# ICEBoard.net
KiCad netlist of a schematic drawn in Altium Designer
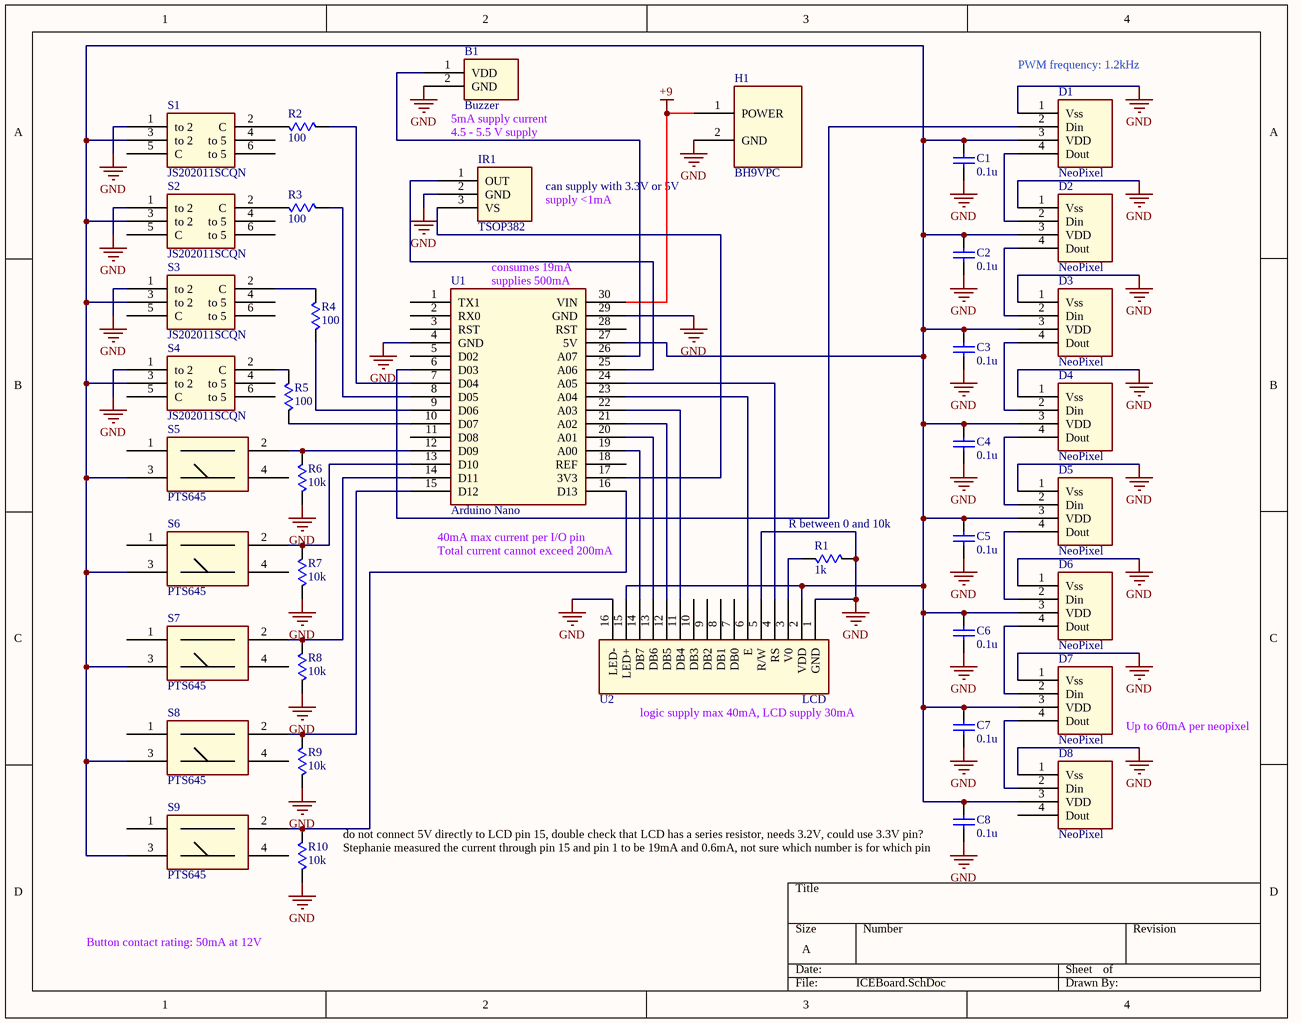
[diagram p0: ICEBoard.SchDoc]

(export (version "E")
  (design (tool "Eeschema 10.0.6"))
  (components
    (comp (ref "B1") (value "Buzzer") (footprint "TP124005") (libsource (lib "TP124005") (part "TP124005")))
    (comp (ref "C1") (value "0.1u") (footprint "Capacitor") (libsource (lib "Capacitor") (part "Capacitor")))
    (comp (ref "C2") (value "0.1u") (footprint "Capacitor") (libsource (lib "Capacitor") (part "Capacitor")))
    (comp (ref "C3") (value "0.1u") (footprint "Capacitor") (libsource (lib "Capacitor") (part "Capacitor")))
    (comp (ref "C4") (value "0.1u") (footprint "Capacitor") (libsource (lib "Capacitor") (part "Capacitor")))
    (comp (ref "C5") (value "0.1u") (footprint "Capacitor") (libsource (lib "Capacitor") (part "Capacitor")))
    (comp (ref "C6") (value "0.1u") (footprint "Capacitor") (libsource (lib "Capacitor") (part "Capacitor")))
    (comp (ref "C7") (value "0.1u") (footprint "Capacitor") (libsource (lib "Capacitor") (part "Capacitor")))
    (comp (ref "C8") (value "0.1u") (footprint "Capacitor") (libsource (lib "Capacitor") (part "Capacitor")))
    (comp (ref "D1") (value "NeoPixel") (footprint "NeoPixel") (libsource (lib "NeoPixel") (part "NeoPixel")))
    (comp (ref "D2") (value "NeoPixel") (footprint "NeoPixel") (libsource (lib "NeoPixel") (part "NeoPixel")))
    (comp (ref "D3") (value "NeoPixel") (footprint "NeoPixel") (libsource (lib "NeoPixel") (part "NeoPixel")))
    (comp (ref "D4") (value "NeoPixel") (footprint "NeoPixel") (libsource (lib "NeoPixel") (part "NeoPixel")))
    (comp (ref "D5") (value "NeoPixel") (footprint "NeoPixel") (libsource (lib "NeoPixel") (part "NeoPixel")))
    (comp (ref "D6") (value "NeoPixel") (footprint "NeoPixel") (libsource (lib "NeoPixel") (part "NeoPixel")))
    (comp (ref "D7") (value "NeoPixel") (footprint "NeoPixel") (libsource (lib "NeoPixel") (part "NeoPixel")))
    (comp (ref "D8") (value "NeoPixel") (footprint "NeoPixel") (libsource (lib "NeoPixel") (part "NeoPixel")))
    (comp (ref "H1") (value "BH9VPC") (footprint "BH9VPC") (libsource (lib "BH9VPC") (part "BH9VPC")))
    (comp (ref "IR1") (value "TSOP382") (footprint "TSOP382") (libsource (lib "TSOP382") (part "TSOP382")))
    (comp (ref "R1") (value "1k") (footprint "Resistor1608") (libsource (lib "Resistor") (part "Resistor")))
    (comp (ref "R2") (value "100") (footprint "Resistor1608") (libsource (lib "Resistor") (part "Resistor")))
    (comp (ref "R3") (value "100") (footprint "Resistor1608") (libsource (lib "Resistor") (part "Resistor")))
    (comp (ref "R4") (value "100") (footprint "Resistor1608") (libsource (lib "Resistor") (part "Resistor")))
    (comp (ref "R5") (value "100") (footprint "Resistor1608") (libsource (lib "Resistor") (part "Resistor")))
    (comp (ref "R6") (value "10k") (footprint "Resistor1608") (libsource (lib "Resistor") (part "Resistor")))
    (comp (ref "R7") (value "10k") (footprint "Resistor1608") (libsource (lib "Resistor") (part "Resistor")))
    (comp (ref "R8") (value "10k") (footprint "Resistor1608") (libsource (lib "Resistor") (part "Resistor")))
    (comp (ref "R9") (value "10k") (footprint "Resistor1608") (libsource (lib "Resistor") (part "Resistor")))
    (comp (ref "R10") (value "10k") (footprint "Resistor1608") (libsource (lib "Resistor") (part "Resistor")))
    (comp (ref "S1")
      (value "JS202011SCQN")
      (footprint "JS202011SCQN")
      (libsource (lib "JS202011SCQN") (part "JS202011SCQN"))
    )
    (comp (ref "S2")
      (value "JS202011SCQN")
      (footprint "JS202011SCQN")
      (libsource (lib "JS202011SCQN") (part "JS202011SCQN"))
    )
    (comp (ref "S3")
      (value "JS202011SCQN")
      (footprint "JS202011SCQN")
      (libsource (lib "JS202011SCQN") (part "JS202011SCQN"))
    )
    (comp (ref "S4")
      (value "JS202011SCQN")
      (footprint "JS202011SCQN")
      (libsource (lib "JS202011SCQN") (part "JS202011SCQN"))
    )
    (comp (ref "S5") (value "PTS645") (footprint "PTS645") (libsource (lib "PTS645") (part "PTS645")))
    (comp (ref "S6") (value "PTS645") (footprint "PTS645") (libsource (lib "PTS645") (part "PTS645")))
    (comp (ref "S7") (value "PTS645") (footprint "PTS645") (libsource (lib "PTS645") (part "PTS645")))
    (comp (ref "S8") (value "PTS645") (footprint "PTS645") (libsource (lib "PTS645") (part "PTS645")))
    (comp (ref "S9") (value "PTS645") (footprint "PTS645") (libsource (lib "PTS645") (part "PTS645")))
    (comp (ref "U1")
      (value "Arduino Nano")
      (footprint "ArduinoNano")
      (libsource (lib "ArduinoNano") (part "ArduinoNano"))
    )
    (comp (ref "U2")
      (value "LCD")
      (footprint "TC1602A-01T")
      (libsource (lib "TC1602A-01T") (part "TC1602A-01T"))
    )
  )
  (nets
    (net (code "1") (name "+9") (class "Default")
      (node (ref "H1") (pin "1") (pinfunction "POWER_1") (pintype "passive"))
      (node (ref "U1") (pin "30") (pinfunction "VIN_30") (pintype "passive"))
    )
    (net (code "2") (name "GND") (class "Default")
      (node (ref "B1") (pin "2") (pinfunction "GND_2") (pintype "passive"))
      (node (ref "C1") (pin "2") (pinfunction "2_2") (pintype "passive"))
      (node (ref "C2") (pin "2") (pinfunction "2_2") (pintype "passive"))
      (node (ref "C3") (pin "2") (pinfunction "2_2") (pintype "passive"))
      (node (ref "C4") (pin "2") (pinfunction "2_2") (pintype "passive"))
      (node (ref "C5") (pin "2") (pinfunction "2_2") (pintype "passive"))
      (node (ref "C6") (pin "2") (pinfunction "2_2") (pintype "passive"))
      (node (ref "C7") (pin "2") (pinfunction "2_2") (pintype "passive"))
      (node (ref "C8") (pin "2") (pinfunction "2_2") (pintype "passive"))
      (node (ref "D1") (pin "1") (pinfunction "Vss_1") (pintype "passive"))
      (node (ref "D2") (pin "1") (pinfunction "Vss_1") (pintype "passive"))
      (node (ref "D3") (pin "1") (pinfunction "Vss_1") (pintype "passive"))
      (node (ref "D4") (pin "1") (pinfunction "Vss_1") (pintype "passive"))
      (node (ref "D5") (pin "1") (pinfunction "Vss_1") (pintype "passive"))
      (node (ref "D6") (pin "1") (pinfunction "Vss_1") (pintype "passive"))
      (node (ref "D7") (pin "1") (pinfunction "Vss_1") (pintype "passive"))
      (node (ref "D8") (pin "1") (pinfunction "Vss_1") (pintype "passive"))
      (node (ref "H1") (pin "2") (pinfunction "GND_2") (pintype "passive"))
      (node (ref "IR1") (pin "2") (pinfunction "GND_2") (pintype "passive"))
      (node (ref "R1") (pin "1") (pinfunction "1_1") (pintype "passive"))
      (node (ref "R10") (pin "1") (pinfunction "1_1") (pintype "passive"))
      (node (ref "R6") (pin "1") (pinfunction "1_1") (pintype "passive"))
      (node (ref "R7") (pin "1") (pinfunction "1_1") (pintype "passive"))
      (node (ref "R8") (pin "1") (pinfunction "1_1") (pintype "passive"))
      (node (ref "R9") (pin "1") (pinfunction "1_1") (pintype "passive"))
      (node (ref "S1") (pin "1") (pinfunction "to_2_1") (pintype "passive"))
      (node (ref "S2") (pin "1") (pinfunction "to_2_1") (pintype "passive"))
      (node (ref "S3") (pin "1") (pinfunction "to_2_1") (pintype "passive"))
      (node (ref "S4") (pin "1") (pinfunction "to_2_1") (pintype "passive"))
      (node (ref "U1") (pin "29") (pinfunction "GND_29") (pintype "passive"))
      (node (ref "U1") (pin "4") (pinfunction "GND_4") (pintype "passive"))
      (node (ref "U2") (pin "1") (pinfunction "GND_1") (pintype "passive"))
      (node (ref "U2") (pin "16") (pinfunction "LED-_16") (pintype "passive"))
      (node (ref "U2") (pin "5") (pinfunction "R/W_5") (pintype "passive"))
    )
    (net (code "3") (name "Net-(B1-VDD)") (class "Default")
      (node (ref "B1") (pin "1") (pinfunction "VDD_1") (pintype "passive"))
      (node (ref "U1") (pin "26") (pinfunction "A07_26") (pintype "passive"))
    )
    (net (code "4") (name "Net-(D1-Din)") (class "Default")
      (node (ref "D1") (pin "2") (pinfunction "Din_2") (pintype "passive"))
      (node (ref "U1") (pin "6") (pinfunction "D03_6") (pintype "passive"))
    )
    (net (code "5") (name "Net-(D1-Dout)") (class "Default")
      (node (ref "D1") (pin "4") (pinfunction "Dout_4") (pintype "passive"))
      (node (ref "D2") (pin "2") (pinfunction "Din_2") (pintype "passive"))
    )
    (net (code "6") (name "Net-(D1-VDD)") (class "Default")
      (node (ref "C1") (pin "1") (pinfunction "1_1") (pintype "passive"))
      (node (ref "C2") (pin "1") (pinfunction "1_1") (pintype "passive"))
      (node (ref "C3") (pin "1") (pinfunction "1_1") (pintype "passive"))
      (node (ref "C4") (pin "1") (pinfunction "1_1") (pintype "passive"))
      (node (ref "C5") (pin "1") (pinfunction "1_1") (pintype "passive"))
      (node (ref "C6") (pin "1") (pinfunction "1_1") (pintype "passive"))
      (node (ref "C7") (pin "1") (pinfunction "1_1") (pintype "passive"))
      (node (ref "C8") (pin "1") (pinfunction "1_1") (pintype "passive"))
      (node (ref "D1") (pin "3") (pinfunction "VDD_3") (pintype "passive"))
      (node (ref "D2") (pin "3") (pinfunction "VDD_3") (pintype "passive"))
      (node (ref "D3") (pin "3") (pinfunction "VDD_3") (pintype "passive"))
      (node (ref "D4") (pin "3") (pinfunction "VDD_3") (pintype "passive"))
      (node (ref "D5") (pin "3") (pinfunction "VDD_3") (pintype "passive"))
      (node (ref "D6") (pin "3") (pinfunction "VDD_3") (pintype "passive"))
      (node (ref "D7") (pin "3") (pinfunction "VDD_3") (pintype "passive"))
      (node (ref "D8") (pin "3") (pinfunction "VDD_3") (pintype "passive"))
      (node (ref "S1") (pin "3") (pinfunction "to_2_3") (pintype "passive"))
      (node (ref "S2") (pin "3") (pinfunction "to_2_3") (pintype "passive"))
      (node (ref "S3") (pin "3") (pinfunction "to_2_3") (pintype "passive"))
      (node (ref "S4") (pin "3") (pinfunction "to_2_3") (pintype "passive"))
      (node (ref "S5") (pin "3") (pintype "passive"))
      (node (ref "S6") (pin "3") (pintype "passive"))
      (node (ref "S7") (pin "3") (pintype "passive"))
      (node (ref "S8") (pin "3") (pintype "passive"))
      (node (ref "S9") (pin "3") (pintype "passive"))
      (node (ref "U1") (pin "27") (pinfunction "5V_27") (pintype "passive"))
      (node (ref "U2") (pin "15") (pinfunction "LED+_15") (pintype "passive"))
      (node (ref "U2") (pin "2") (pinfunction "VDD_2") (pintype "passive"))
    )
    (net (code "7") (name "Net-(D2-Dout)") (class "Default")
      (node (ref "D2") (pin "4") (pinfunction "Dout_4") (pintype "passive"))
      (node (ref "D3") (pin "2") (pinfunction "Din_2") (pintype "passive"))
    )
    (net (code "8") (name "Net-(D3-Dout)") (class "Default")
      (node (ref "D3") (pin "4") (pinfunction "Dout_4") (pintype "passive"))
      (node (ref "D4") (pin "2") (pinfunction "Din_2") (pintype "passive"))
    )
    (net (code "9") (name "Net-(D4-Dout)") (class "Default")
      (node (ref "D4") (pin "4") (pinfunction "Dout_4") (pintype "passive"))
      (node (ref "D5") (pin "2") (pinfunction "Din_2") (pintype "passive"))
    )
    (net (code "10") (name "Net-(D5-Dout)") (class "Default")
      (node (ref "D5") (pin "4") (pinfunction "Dout_4") (pintype "passive"))
      (node (ref "D6") (pin "2") (pinfunction "Din_2") (pintype "passive"))
    )
    (net (code "11") (name "Net-(D6-Dout)") (class "Default")
      (node (ref "D6") (pin "4") (pinfunction "Dout_4") (pintype "passive"))
      (node (ref "D7") (pin "2") (pinfunction "Din_2") (pintype "passive"))
    )
    (net (code "12") (name "Net-(D7-Dout)") (class "Default")
      (node (ref "D7") (pin "4") (pinfunction "Dout_4") (pintype "passive"))
      (node (ref "D8") (pin "2") (pinfunction "Din_2") (pintype "passive"))
    )
    (net (code "13") (name "Net-(IR1-OUT)") (class "Default")
      (node (ref "IR1") (pin "1") (pinfunction "OUT_1") (pintype "passive"))
      (node (ref "U1") (pin "25") (pinfunction "A06_25") (pintype "passive"))
    )
    (net (code "14") (name "Net-(IR1-VS)") (class "Default")
      (node (ref "IR1") (pin "3") (pinfunction "VS_3") (pintype "passive"))
      (node (ref "U1") (pin "17") (pinfunction "3V3_17") (pintype "passive"))
    )
    (net (code "15") (name "Net-(R2-Pad2)") (class "Default")
      (node (ref "R2") (pin "2") (pinfunction "2_2") (pintype "passive"))
      (node (ref "S1") (pin "2") (pinfunction "C_2") (pintype "passive"))
    )
    (net (code "16") (name "Net-(R3-Pad2)") (class "Default")
      (node (ref "R3") (pin "2") (pinfunction "2_2") (pintype "passive"))
      (node (ref "S2") (pin "2") (pinfunction "C_2") (pintype "passive"))
    )
    (net (code "17") (name "Net-(R4-Pad2)") (class "Default")
      (node (ref "R4") (pin "2") (pinfunction "2_2") (pintype "passive"))
      (node (ref "S3") (pin "2") (pinfunction "C_2") (pintype "passive"))
    )
    (net (code "18") (name "Net-(R5-Pad2)") (class "Default")
      (node (ref "R5") (pin "2") (pinfunction "2_2") (pintype "passive"))
      (node (ref "S4") (pin "2") (pinfunction "C_2") (pintype "passive"))
    )
    (net (code "19") (name "Net-(U1-A00)") (class "Default")
      (node (ref "U1") (pin "19") (pinfunction "A00_19") (pintype "passive"))
      (node (ref "U2") (pin "14") (pinfunction "DB7_14") (pintype "passive"))
    )
    (net (code "20") (name "Net-(U1-A01)") (class "Default")
      (node (ref "U1") (pin "20") (pinfunction "A01_20") (pintype "passive"))
      (node (ref "U2") (pin "13") (pinfunction "DB6_13") (pintype "passive"))
    )
    (net (code "21") (name "Net-(U1-A02)") (class "Default")
      (node (ref "U1") (pin "21") (pinfunction "A02_21") (pintype "passive"))
      (node (ref "U2") (pin "12") (pinfunction "DB5_12") (pintype "passive"))
    )
    (net (code "22") (name "Net-(U1-A03)") (class "Default")
      (node (ref "U1") (pin "22") (pinfunction "A03_22") (pintype "passive"))
      (node (ref "U2") (pin "11") (pinfunction "DB4_11") (pintype "passive"))
    )
    (net (code "23") (name "Net-(U1-A04)") (class "Default")
      (node (ref "U1") (pin "23") (pinfunction "A04_23") (pintype "passive"))
      (node (ref "U2") (pin "6") (pinfunction "E_6") (pintype "passive"))
    )
    (net (code "24") (name "Net-(U1-A05)") (class "Default")
      (node (ref "U1") (pin "24") (pinfunction "A05_24") (pintype "passive"))
      (node (ref "U2") (pin "4") (pinfunction "RS_4") (pintype "passive"))
    )
    (net (code "25") (name "Net-(U1-D04)") (class "Default")
      (node (ref "R2") (pin "1") (pinfunction "1_1") (pintype "passive"))
      (node (ref "U1") (pin "7") (pinfunction "D04_7") (pintype "passive"))
    )
    (net (code "26") (name "Net-(U1-D05)") (class "Default")
      (node (ref "R3") (pin "1") (pinfunction "1_1") (pintype "passive"))
      (node (ref "U1") (pin "8") (pinfunction "D05_8") (pintype "passive"))
    )
    (net (code "27") (name "Net-(U1-D06)") (class "Default")
      (node (ref "R4") (pin "1") (pinfunction "1_1") (pintype "passive"))
      (node (ref "U1") (pin "9") (pinfunction "D06_9") (pintype "passive"))
    )
    (net (code "28") (name "Net-(U1-D07)") (class "Default")
      (node (ref "R5") (pin "1") (pinfunction "1_1") (pintype "passive"))
      (node (ref "U1") (pin "10") (pinfunction "D07_10") (pintype "passive"))
    )
    (net (code "29") (name "Net-(U1-D09)") (class "Default")
      (node (ref "R6") (pin "2") (pinfunction "2_2") (pintype "passive"))
      (node (ref "S5") (pin "2") (pintype "passive"))
      (node (ref "U1") (pin "12") (pinfunction "D09_12") (pintype "passive"))
    )
    (net (code "30") (name "Net-(U1-D10)") (class "Default")
      (node (ref "R7") (pin "2") (pinfunction "2_2") (pintype "passive"))
      (node (ref "S6") (pin "2") (pintype "passive"))
      (node (ref "U1") (pin "13") (pinfunction "D10_13") (pintype "passive"))
    )
    (net (code "31") (name "Net-(U1-D11)") (class "Default")
      (node (ref "R8") (pin "2") (pinfunction "2_2") (pintype "passive"))
      (node (ref "S7") (pin "2") (pintype "passive"))
      (node (ref "U1") (pin "14") (pinfunction "D11_14") (pintype "passive"))
    )
    (net (code "32") (name "Net-(U1-D12)") (class "Default")
      (node (ref "R9") (pin "2") (pinfunction "2_2") (pintype "passive"))
      (node (ref "S8") (pin "2") (pintype "passive"))
      (node (ref "U1") (pin "15") (pinfunction "D12_15") (pintype "passive"))
    )
    (net (code "33") (name "Net-(U1-D13)") (class "Default")
      (node (ref "R10") (pin "2") (pinfunction "2_2") (pintype "passive"))
      (node (ref "S9") (pin "2") (pintype "passive"))
      (node (ref "U1") (pin "16") (pinfunction "D13_16") (pintype "passive"))
    )
    (net (code "34") (name "Net-(U2-V0)") (class "Default")
      (node (ref "R1") (pin "2") (pinfunction "2_2") (pintype "passive"))
      (node (ref "U2") (pin "3") (pinfunction "V0_3") (pintype "passive"))
    )
    (net (code "35") (name "unconnected-(D8-Dout-Pad4)") (class "Default")
      (node (ref "D8") (pin "4") (pinfunction "Dout_4") (pintype "passive"))
    )
    (net (code "36") (name "unconnected-(S1-C-Pad5)") (class "Default")
      (node (ref "S1") (pin "5") (pinfunction "C_5") (pintype "passive"))
    )
    (net (code "37") (name "unconnected-(S1-to_5-Pad4)") (class "Default")
      (node (ref "S1") (pin "4") (pinfunction "to_5_4") (pintype "passive"))
    )
    (net (code "38") (name "unconnected-(S1-to_5-Pad6)") (class "Default")
      (node (ref "S1") (pin "6") (pinfunction "to_5_6") (pintype "passive"))
    )
    (net (code "39") (name "unconnected-(S2-C-Pad5)") (class "Default")
      (node (ref "S2") (pin "5") (pinfunction "C_5") (pintype "passive"))
    )
    (net (code "40") (name "unconnected-(S2-to_5-Pad4)") (class "Default")
      (node (ref "S2") (pin "4") (pinfunction "to_5_4") (pintype "passive"))
    )
    (net (code "41") (name "unconnected-(S2-to_5-Pad6)") (class "Default")
      (node (ref "S2") (pin "6") (pinfunction "to_5_6") (pintype "passive"))
    )
    (net (code "42") (name "unconnected-(S3-C-Pad5)") (class "Default")
      (node (ref "S3") (pin "5") (pinfunction "C_5") (pintype "passive"))
    )
    (net (code "43") (name "unconnected-(S3-to_5-Pad4)") (class "Default")
      (node (ref "S3") (pin "4") (pinfunction "to_5_4") (pintype "passive"))
    )
    (net (code "44") (name "unconnected-(S3-to_5-Pad6)") (class "Default")
      (node (ref "S3") (pin "6") (pinfunction "to_5_6") (pintype "passive"))
    )
    (net (code "45") (name "unconnected-(S4-C-Pad5)") (class "Default")
      (node (ref "S4") (pin "5") (pinfunction "C_5") (pintype "passive"))
    )
    (net (code "46") (name "unconnected-(S4-to_5-Pad4)") (class "Default")
      (node (ref "S4") (pin "4") (pinfunction "to_5_4") (pintype "passive"))
    )
    (net (code "47") (name "unconnected-(S4-to_5-Pad6)") (class "Default")
      (node (ref "S4") (pin "6") (pinfunction "to_5_6") (pintype "passive"))
    )
    (net (code "48") (name "unconnected-(S5-Pad1)") (class "Default")
      (node (ref "S5") (pin "1") (pintype "passive"))
    )
    (net (code "49") (name "unconnected-(S5-Pad4)") (class "Default")
      (node (ref "S5") (pin "4") (pintype "passive"))
    )
    (net (code "50") (name "unconnected-(S6-Pad1)") (class "Default")
      (node (ref "S6") (pin "1") (pintype "passive"))
    )
    (net (code "51") (name "unconnected-(S6-Pad4)") (class "Default")
      (node (ref "S6") (pin "4") (pintype "passive"))
    )
    (net (code "52") (name "unconnected-(S7-Pad1)") (class "Default")
      (node (ref "S7") (pin "1") (pintype "passive"))
    )
    (net (code "53") (name "unconnected-(S7-Pad4)") (class "Default")
      (node (ref "S7") (pin "4") (pintype "passive"))
    )
    (net (code "54") (name "unconnected-(S8-Pad1)") (class "Default")
      (node (ref "S8") (pin "1") (pintype "passive"))
    )
    (net (code "55") (name "unconnected-(S8-Pad4)") (class "Default")
      (node (ref "S8") (pin "4") (pintype "passive"))
    )
    (net (code "56") (name "unconnected-(S9-Pad1)") (class "Default")
      (node (ref "S9") (pin "1") (pintype "passive"))
    )
    (net (code "57") (name "unconnected-(S9-Pad4)") (class "Default")
      (node (ref "S9") (pin "4") (pintype "passive"))
    )
    (net (code "58") (name "unconnected-(U1-D02-Pad5)") (class "Default")
      (node (ref "U1") (pin "5") (pinfunction "D02_5") (pintype "passive"))
    )
    (net (code "59") (name "unconnected-(U1-D08-Pad11)") (class "Default")
      (node (ref "U1") (pin "11") (pinfunction "D08_11") (pintype "passive"))
    )
    (net (code "60") (name "unconnected-(U1-REF-Pad18)") (class "Default")
      (node (ref "U1") (pin "18") (pinfunction "REF_18") (pintype "passive"))
    )
    (net (code "61") (name "unconnected-(U1-RST-Pad3)") (class "Default")
      (node (ref "U1") (pin "3") (pinfunction "RST_3") (pintype "passive"))
    )
    (net (code "62") (name "unconnected-(U1-RST-Pad28)") (class "Default")
      (node (ref "U1") (pin "28") (pinfunction "RST_28") (pintype "passive"))
    )
    (net (code "63") (name "unconnected-(U1-RX0-Pad2)") (class "Default")
      (node (ref "U1") (pin "2") (pinfunction "RX0_2") (pintype "passive"))
    )
    (net (code "64") (name "unconnected-(U1-TX1-Pad1)") (class "Default")
      (node (ref "U1") (pin "1") (pinfunction "TX1_1") (pintype "passive"))
    )
    (net (code "65") (name "unconnected-(U2-DB0-Pad7)") (class "Default")
      (node (ref "U2") (pin "7") (pinfunction "DB0_7") (pintype "passive"))
    )
    (net (code "66") (name "unconnected-(U2-DB1-Pad8)") (class "Default")
      (node (ref "U2") (pin "8") (pinfunction "DB1_8") (pintype "passive"))
    )
    (net (code "67") (name "unconnected-(U2-DB2-Pad9)") (class "Default")
      (node (ref "U2") (pin "9") (pinfunction "DB2_9") (pintype "passive"))
    )
    (net (code "68") (name "unconnected-(U2-DB3-Pad10)") (class "Default")
      (node (ref "U2") (pin "10") (pinfunction "DB3_10") (pintype "passive"))
    )
  )
)
